# Solenoid_Driver.net
KiCad netlist of a schematic drawn in EAGLE
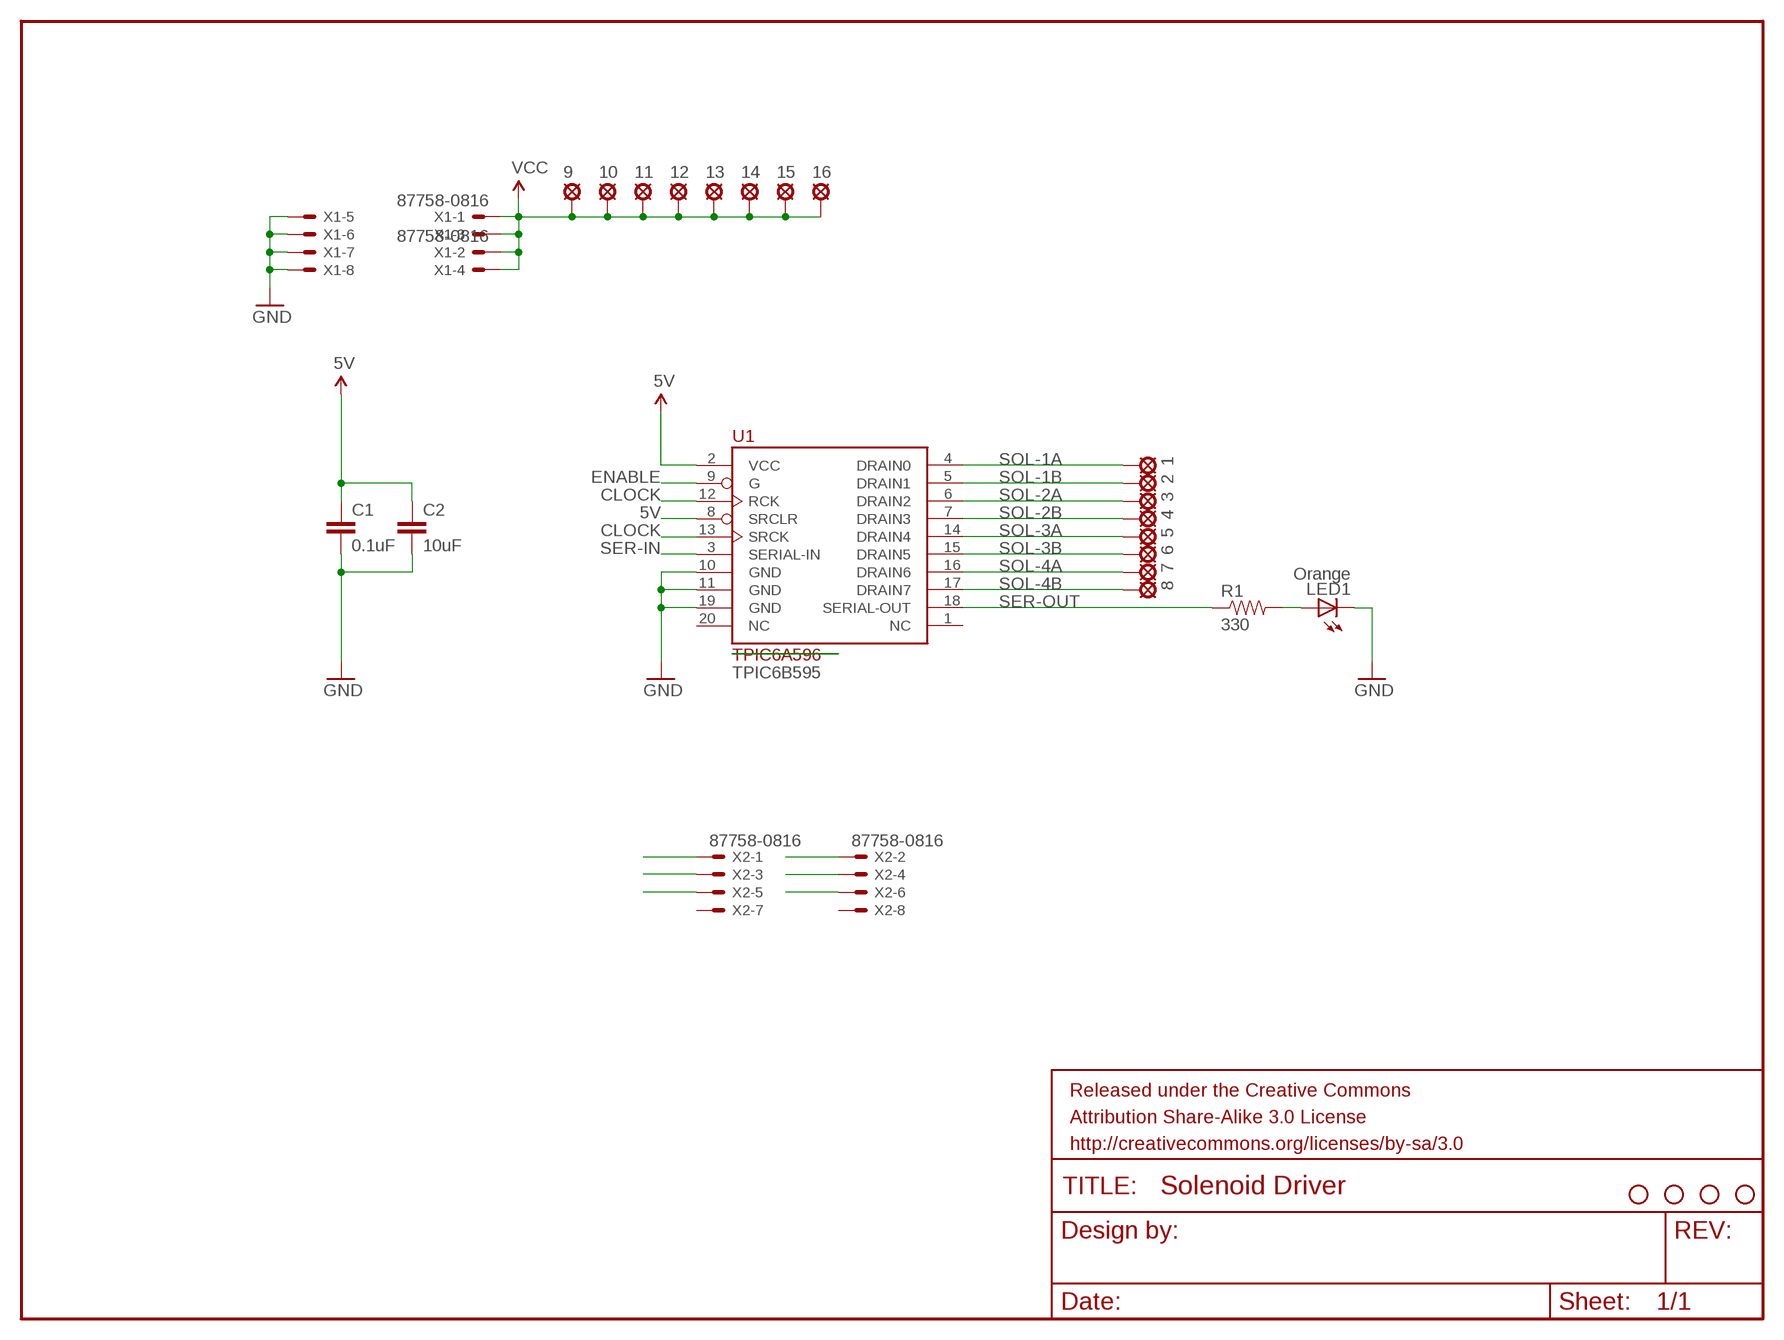
[diagram p0: schematic, sheet 1]

(export (version "E")
  (design (tool "Eeschema 10.0.6"))
  (components
    (comp (ref "1")
      (value "SE14")
      (footprint "eagle-import:SE14")
      (libsource (lib "eagle-import") (part "SE14"))
    )
    (comp (ref "2")
      (value "SE14")
      (footprint "eagle-import:SE14")
      (libsource (lib "eagle-import") (part "SE14"))
    )
    (comp (ref "3")
      (value "SE14")
      (footprint "eagle-import:SE14")
      (libsource (lib "eagle-import") (part "SE14"))
    )
    (comp (ref "4")
      (value "SE14")
      (footprint "eagle-import:SE14")
      (libsource (lib "eagle-import") (part "SE14"))
    )
    (comp (ref "5")
      (value "SE14")
      (footprint "eagle-import:SE14")
      (libsource (lib "eagle-import") (part "SE14"))
    )
    (comp (ref "6")
      (value "SE14")
      (footprint "eagle-import:SE14")
      (libsource (lib "eagle-import") (part "SE14"))
    )
    (comp (ref "7")
      (value "SE14")
      (footprint "eagle-import:SE14")
      (libsource (lib "eagle-import") (part "SE14"))
    )
    (comp (ref "8")
      (value "SE14")
      (footprint "eagle-import:SE14")
      (libsource (lib "eagle-import") (part "SE14"))
    )
    (comp (ref "9")
      (value "SE14")
      (footprint "eagle-import:SE14")
      (libsource (lib "eagle-import") (part "SE14"))
    )
    (comp (ref "10")
      (value "SE14")
      (footprint "eagle-import:SE14")
      (libsource (lib "eagle-import") (part "SE14"))
    )
    (comp (ref "11")
      (value "SE14")
      (footprint "eagle-import:SE14")
      (libsource (lib "eagle-import") (part "SE14"))
    )
    (comp (ref "12")
      (value "SE14")
      (footprint "eagle-import:SE14")
      (libsource (lib "eagle-import") (part "SE14"))
    )
    (comp (ref "13")
      (value "SE14")
      (footprint "eagle-import:SE14")
      (libsource (lib "eagle-import") (part "SE14"))
    )
    (comp (ref "14")
      (value "SE14")
      (footprint "eagle-import:SE14")
      (libsource (lib "eagle-import") (part "SE14"))
    )
    (comp (ref "15")
      (value "SE14")
      (footprint "eagle-import:SE14")
      (libsource (lib "eagle-import") (part "SE14"))
    )
    (comp (ref "16")
      (value "SE14")
      (footprint "eagle-import:SE14")
      (libsource (lib "eagle-import") (part "SE14"))
    )
    (comp (ref "C1")
      (value "0.1uF")
      (footprint "eagle-import:0603-CAP")
      (libsource (lib "eagle-import") (part "CAP0603-CAP"))
    )
    (comp (ref "C2")
      (value "10uF")
      (footprint "eagle-import:0603-CAP")
      (libsource (lib "eagle-import") (part "CAP0603-CAP"))
    )
    (comp (ref "JP1")
      (value "STAND-OFF")
      (footprint "eagle-import:STAND-OFF")
      (libsource (lib "eagle-import") (part "STAND-OFF"))
    )
    (comp (ref "JP2")
      (value "STAND-OFF")
      (footprint "eagle-import:STAND-OFF")
      (libsource (lib "eagle-import") (part "STAND-OFF"))
    )
    (comp (ref "JP3")
      (value "STAND-OFF")
      (footprint "eagle-import:STAND-OFF")
      (libsource (lib "eagle-import") (part "STAND-OFF"))
    )
    (comp (ref "JP4")
      (value "STAND-OFF")
      (footprint "eagle-import:STAND-OFF")
      (libsource (lib "eagle-import") (part "STAND-OFF"))
    )
    (comp (ref "LED1")
      (value "Orange")
      (footprint "eagle-import:LED-0603")
      (libsource (lib "eagle-import") (part "LED0603"))
    )
    (comp (ref "R1")
      (value "330")
      (footprint "eagle-import:0603-RES")
      (libsource (lib "eagle-import") (part "RESISTOR0603-RES"))
    )
    (comp (ref "U1")
      (value "TPIC6A596")
      (footprint "eagle-import:SOIC20-W")
      (libsource (lib "eagle-import") (part "TPIC6A596"))
    )
    (comp (ref "X1")
      (value "87758-0816")
      (footprint "eagle-import:87758-0816")
      (fields (field (name "MF") "MOLEX"))
      (libsource (lib "eagle-import") (part "87758-0816"))
    )
    (comp (ref "X2")
      (value "87758-0816")
      (footprint "eagle-import:87758-0816")
      (fields (field (name "MF") "MOLEX"))
      (libsource (lib "eagle-import") (part "87758-0816"))
    )
  )
  (nets
    (net (code "1") (name "/CLOCK") (class "Default")
      (node (ref "U1") (pin "12") (pinfunction "RCK_12") (pintype "bidirectional"))
      (node (ref "U1") (pin "13") (pinfunction "SRCK_13") (pintype "bidirectional"))
      (node (ref "X2") (pin "2") (pinfunction "S_2") (pintype "passive"))
    )
    (net (code "2") (name "/ENABLE") (class "Default")
      (node (ref "U1") (pin "9") (pinfunction "G_9") (pintype "bidirectional"))
      (node (ref "X2") (pin "4") (pinfunction "S_4") (pintype "passive"))
    )
    (net (code "3") (name "/SER-IN") (class "Default")
      (node (ref "U1") (pin "3") (pinfunction "SERIAL-IN_3") (pintype "bidirectional"))
      (node (ref "X2") (pin "6") (pinfunction "S_6") (pintype "passive"))
    )
    (net (code "4") (name "/SER-OUT") (class "Default")
      (node (ref "R1") (pin "1") (pinfunction "1_1") (pintype "passive"))
      (node (ref "U1") (pin "18") (pinfunction "SERIAL-OUT_18") (pintype "bidirectional"))
    )
    (net (code "5") (name "/SOL-1A") (class "Default")
      (node (ref "1") (pin "MP") (pinfunction "MP_MP") (pintype "passive"))
      (node (ref "U1") (pin "4") (pinfunction "DRAIN0_4") (pintype "bidirectional"))
    )
    (net (code "6") (name "/SOL-1B") (class "Default")
      (node (ref "2") (pin "MP") (pinfunction "MP_MP") (pintype "passive"))
      (node (ref "U1") (pin "5") (pinfunction "DRAIN1_5") (pintype "bidirectional"))
    )
    (net (code "7") (name "/SOL-2A") (class "Default")
      (node (ref "3") (pin "MP") (pinfunction "MP_MP") (pintype "passive"))
      (node (ref "U1") (pin "6") (pinfunction "DRAIN2_6") (pintype "bidirectional"))
    )
    (net (code "8") (name "/SOL-2B") (class "Default")
      (node (ref "4") (pin "MP") (pinfunction "MP_MP") (pintype "passive"))
      (node (ref "U1") (pin "7") (pinfunction "DRAIN3_7") (pintype "bidirectional"))
    )
    (net (code "9") (name "/SOL-3A") (class "Default")
      (node (ref "5") (pin "MP") (pinfunction "MP_MP") (pintype "passive"))
      (node (ref "U1") (pin "14") (pinfunction "DRAIN4_14") (pintype "bidirectional"))
    )
    (net (code "10") (name "/SOL-3B") (class "Default")
      (node (ref "6") (pin "MP") (pinfunction "MP_MP") (pintype "passive"))
      (node (ref "U1") (pin "15") (pinfunction "DRAIN5_15") (pintype "bidirectional"))
    )
    (net (code "11") (name "/SOL-4A") (class "Default")
      (node (ref "7") (pin "MP") (pinfunction "MP_MP") (pintype "passive"))
      (node (ref "U1") (pin "16") (pinfunction "DRAIN6_16") (pintype "bidirectional"))
    )
    (net (code "12") (name "/SOL-4B") (class "Default")
      (node (ref "8") (pin "MP") (pinfunction "MP_MP") (pintype "passive"))
      (node (ref "U1") (pin "17") (pinfunction "DRAIN7_17") (pintype "bidirectional"))
    )
    (net (code "13") (name "5V") (class "Default")
      (node (ref "C1") (pin "1") (pinfunction "1_1") (pintype "passive"))
      (node (ref "C2") (pin "1") (pinfunction "1_1") (pintype "passive"))
      (node (ref "U1") (pin "2") (pinfunction "VCC_2") (pintype "bidirectional"))
      (node (ref "U1") (pin "8") (pinfunction "SRCLR_8") (pintype "bidirectional"))
      (node (ref "X2") (pin "5") (pinfunction "S_5") (pintype "passive"))
    )
    (net (code "14") (name "GND") (class "Default")
      (node (ref "C1") (pin "2") (pinfunction "2_2") (pintype "passive"))
      (node (ref "C2") (pin "2") (pinfunction "2_2") (pintype "passive"))
      (node (ref "LED1") (pin "C") (pinfunction "C_C") (pintype "passive"))
      (node (ref "U1") (pin "10") (pinfunction "GND_10") (pintype "bidirectional"))
      (node (ref "U1") (pin "11") (pinfunction "GND_11") (pintype "bidirectional"))
      (node (ref "U1") (pin "19") (pinfunction "GND_19") (pintype "bidirectional"))
      (node (ref "X1") (pin "5") (pinfunction "S_5") (pintype "passive"))
      (node (ref "X1") (pin "6") (pinfunction "S_6") (pintype "passive"))
      (node (ref "X1") (pin "7") (pinfunction "S_7") (pintype "passive"))
      (node (ref "X1") (pin "8") (pinfunction "S_8") (pintype "passive"))
      (node (ref "X2") (pin "1") (pinfunction "S_1") (pintype "passive"))
      (node (ref "X2") (pin "3") (pinfunction "S_3") (pintype "passive"))
    )
    (net (code "15") (name "Net-(LED1-PadA)") (class "Default")
      (node (ref "LED1") (pin "A") (pinfunction "A_A") (pintype "passive"))
      (node (ref "R1") (pin "2") (pinfunction "2_2") (pintype "passive"))
    )
    (net (code "16") (name "VCC") (class "Default")
      (node (ref "10") (pin "MP") (pinfunction "MP_MP") (pintype "passive"))
      (node (ref "11") (pin "MP") (pinfunction "MP_MP") (pintype "passive"))
      (node (ref "12") (pin "MP") (pinfunction "MP_MP") (pintype "passive"))
      (node (ref "13") (pin "MP") (pinfunction "MP_MP") (pintype "passive"))
      (node (ref "14") (pin "MP") (pinfunction "MP_MP") (pintype "passive"))
      (node (ref "15") (pin "MP") (pinfunction "MP_MP") (pintype "passive"))
      (node (ref "16") (pin "MP") (pinfunction "MP_MP") (pintype "passive"))
      (node (ref "9") (pin "MP") (pinfunction "MP_MP") (pintype "passive"))
      (node (ref "X1") (pin "1") (pinfunction "S_1") (pintype "passive"))
      (node (ref "X1") (pin "2") (pinfunction "S_2") (pintype "passive"))
      (node (ref "X1") (pin "3") (pinfunction "S_3") (pintype "passive"))
      (node (ref "X1") (pin "4") (pinfunction "S_4") (pintype "passive"))
    )
    (net (code "17") (name "unconnected-(U1-NC-Pad1)") (class "Default")
      (node (ref "U1") (pin "1") (pinfunction "NC_1") (pintype "bidirectional"))
    )
    (net (code "18") (name "unconnected-(U1-NC-Pad20)") (class "Default")
      (node (ref "U1") (pin "20") (pinfunction "NC_20") (pintype "bidirectional"))
    )
    (net (code "19") (name "unconnected-(X2G-S-Pad7)") (class "Default")
      (node (ref "X2") (pin "7") (pinfunction "S_7") (pintype "passive"))
    )
    (net (code "20") (name "unconnected-(X2H-S-Pad8)") (class "Default")
      (node (ref "X2") (pin "8") (pinfunction "S_8") (pintype "passive"))
    )
  )
)
